# ACCELEROMETER.net
KiCad netlist of a schematic drawn in Altium Designer
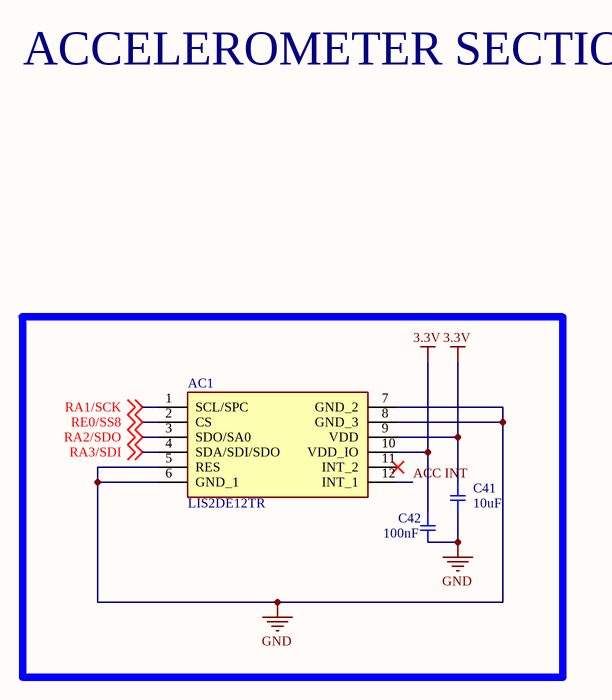
[diagram p0: ACCELEROMETER.SchDoc]

(export (version "E")
  (design (tool "Eeschema 10.0.6"))
  (components
    (comp (ref "AC1")
      (value "LIS2DE12TR")
      (footprint "SamacSys:LIS2DE12TR")
      (description "Accelerometer")
      (fields (field (name "MOUSER PART NUMBER") "511-LIS2DE12TR"))
      (libsource (lib "*") (part "LIS2DE12TR"))
    )
    (comp (ref "C41")
      (value "10uF")
      (footprint "SMD-0805C")
      (description "CAP CER 0.1UF 50V X7R 0805")
      (fields
        (field (name "DIGI-KEY PART NUMBER") "490-11955-1-ND")
        (field (name "PART NUMBER") "GCD21BR71H104KA01L")
      )
      (libsource (lib "capacitor_murata_0805") (part "GCD21BR71H104KA01L"))
    )
    (comp (ref "C42")
      (value "100nF")
      (footprint "SMD-0805C")
      (description "CAP CER 0.1UF 50V X7R 0805")
      (fields
        (field (name "DIGI-KEY PART NUMBER") "490-11955-1-ND")
        (field (name "PART NUMBER") "GCD21BR71H104KA01L")
      )
      (libsource (lib "capacitor_murata_0805") (part "GCD21BR71H104KA01L"))
    )
  )
  (nets
    (net (code "1") (name "/ACC INT") (class "Default")
      (node (ref "AC1") (pin "12") (pinfunction "INT_1_12") (pintype "passive"))
    )
    (net (code "2") (name "3.3V") (class "Default")
      (node (ref "AC1") (pin "10") (pinfunction "VDD_IO_10") (pintype "passive"))
      (node (ref "AC1") (pin "9") (pinfunction "VDD_9") (pintype "passive"))
      (node (ref "C41") (pin "1") (pinfunction "1_1") (pintype "passive"))
      (node (ref "C42") (pin "1") (pinfunction "1_1") (pintype "passive"))
    )
    (net (code "3") (name "GND") (class "Default")
      (node (ref "AC1") (pin "5") (pinfunction "RES_5") (pintype "passive"))
      (node (ref "AC1") (pin "6") (pinfunction "GND_1_6") (pintype "passive"))
      (node (ref "AC1") (pin "7") (pinfunction "GND_2_7") (pintype "passive"))
      (node (ref "AC1") (pin "8") (pinfunction "GND_3_8") (pintype "passive"))
      (node (ref "C41") (pin "2") (pinfunction "2_2") (pintype "passive"))
      (node (ref "C42") (pin "2") (pinfunction "2_2") (pintype "passive"))
    )
    (net (code "4") (name "RA1{slash}SCK") (class "Default")
      (node (ref "AC1") (pin "1") (pinfunction "SCL/SPC_1") (pintype "passive"))
    )
    (net (code "5") (name "RA2{slash}SDO") (class "Default")
      (node (ref "AC1") (pin "3") (pinfunction "SDO/SA0_3") (pintype "passive"))
    )
    (net (code "6") (name "RA3{slash}SDI") (class "Default")
      (node (ref "AC1") (pin "4") (pinfunction "SDA/SDI/SDO_4") (pintype "passive"))
    )
    (net (code "7") (name "RE0{slash}SS8") (class "Default")
      (node (ref "AC1") (pin "2") (pinfunction "CS_2") (pintype "passive"))
    )
    (net (code "8") (name "unconnected-(AC1-INT_2-Pad11)") (class "Default")
      (node (ref "AC1") (pin "11") (pinfunction "INT_2_11") (pintype "passive+no_connect"))
    )
  )
)
